# Sheet1.net
KiCad netlist of a schematic drawn in Altium Designer
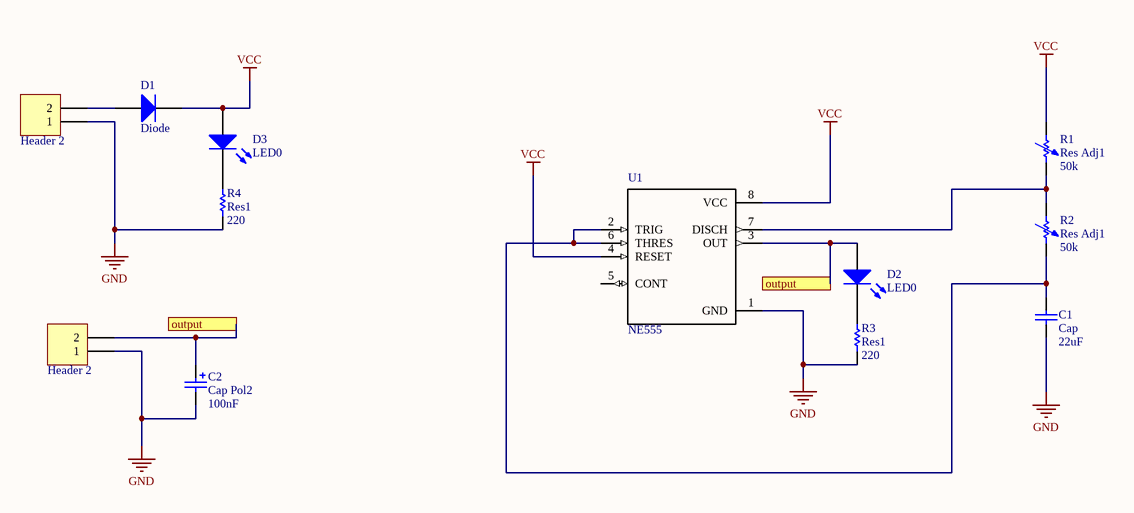
[diagram p0: Sheet1.SchDoc]

(export (version "E")
  (design (tool "Eeschema 10.0.6"))
  (components
    (comp (ref "C1")
      (value "Cap")
      (footprint "RAD-0.2")
      (description "Capacitor")
      (fields (field (name "ALTIUM_VALUE") "22uF") (field (name "PUBLISHER") "Altium Limited"))
      (libsource (lib "Miscellaneous Devices") (part "Cap"))
    )
    (comp (ref "C2")
      (value "Cap Pol2")
      (footprint "RAD-0.2")
      (description "Polarized Capacitor (Axial)")
      (fields (field (name "ALTIUM_VALUE") "100nF") (field (name "PUBLISHER") "Altium Limited"))
      (libsource (lib "Miscellaneous Devices") (part "Cap Pol2"))
    )
    (comp (ref "D1")
      (value "Diode")
      (footprint "DIODE-0.4")
      (description "Default Diode")
      (fields (field (name "PUBLISHER") "Altium Limited"))
      (libsource (lib "Miscellaneous Devices") (part "Diode"))
    )
    (comp (ref "D2")
      (value "LED0")
      (footprint "HDR1X2")
      (description "Typical INFRARED GaAs LED")
      (fields (field (name "PUBLISHER") "Altium Limited"))
      (libsource (lib "Miscellaneous Devices") (part "LED0"))
    )
    (comp (ref "D3")
      (value "LED0")
      (footprint "HDR1X2")
      (description "Typical INFRARED GaAs LED")
      (fields (field (name "PUBLISHER") "Altium Limited"))
      (libsource (lib "Miscellaneous Devices") (part "LED0"))
    )
    (comp (ref "P1")
      (value "Header 2")
      (footprint "CN_KRE_2")
      (description "Header, 2-Pin")
      (fields (field (name "PUBLISHER") "Altium Limited"))
      (libsource (lib "Miscellaneous Connectors") (part "Header 2"))
    )
    (comp (ref "P2")
      (value "Header 2")
      (footprint "CN_KRE_2")
      (description "Header, 2-Pin")
      (fields (field (name "PUBLISHER") "Altium Limited"))
      (libsource (lib "Miscellaneous Connectors") (part "Header 2"))
    )
    (comp (ref "R1")
      (value "Res Adj1")
      (footprint "CN_KRE_3")
      (description "Variable Resistor")
      (fields (field (name "ALTIUM_VALUE") "50k") (field (name "PUBLISHER") "Altium Limited"))
      (libsource (lib "Miscellaneous Devices") (part "Res Adj1"))
    )
    (comp (ref "R2")
      (value "Res Adj1")
      (footprint "CN_KRE_3")
      (description "Variable Resistor")
      (fields (field (name "ALTIUM_VALUE") "50k") (field (name "PUBLISHER") "Altium Limited"))
      (libsource (lib "Miscellaneous Devices") (part "Res Adj1"))
    )
    (comp (ref "R3")
      (value "Res1")
      (footprint "AXIAL-0.3")
      (description "Resistor")
      (fields (field (name "ALTIUM_VALUE") "220") (field (name "PUBLISHER") "Altium Limited"))
      (libsource (lib "Miscellaneous Devices") (part "Res1"))
    )
    (comp (ref "R4")
      (value "Res1")
      (footprint "AXIAL-0.3")
      (description "Resistor")
      (fields (field (name "ALTIUM_VALUE") "220") (field (name "PUBLISHER") "Altium Limited"))
      (libsource (lib "Miscellaneous Devices") (part "Res1"))
    )
    (comp (ref "U1")
      (value "NE555")
      (footprint "*DIP794W45P254L1060H508Q8")
      (fields (field (name "MF") "Texas Instruments") (field (name "DIGI-KEY_PART_NUMBER") "296-6501-1-ND"))
      (libsource (lib "NE555") (part "NE555"))
    )
  )
  (nets
    (net (code "1") (name "/output") (class "Default")
      (node (ref "C2") (pin "1") (pinfunction "1_1") (pintype "passive"))
      (node (ref "D2") (pin "1") (pinfunction "A_1") (pintype "passive"))
      (node (ref "P2") (pin "2") (pinfunction "2_2") (pintype "passive"))
      (node (ref "U1") (pin "3") (pinfunction "OUT_3") (pintype "output"))
    )
    (net (code "2") (name "GND") (class "Default")
      (node (ref "C1") (pin "1") (pinfunction "1_1") (pintype "passive"))
      (node (ref "C2") (pin "2") (pinfunction "2_2") (pintype "passive"))
      (node (ref "P1") (pin "1") (pinfunction "1_1") (pintype "passive"))
      (node (ref "P2") (pin "1") (pinfunction "1_1") (pintype "passive"))
      (node (ref "R3") (pin "1") (pinfunction "1_1") (pintype "passive"))
      (node (ref "R4") (pin "1") (pinfunction "1_1") (pintype "passive"))
      (node (ref "U1") (pin "1") (pinfunction "GND_1") (pintype "power_in"))
    )
    (net (code "3") (name "Net-(D1-A)") (class "Default")
      (node (ref "D1") (pin "1") (pinfunction "A_1") (pintype "passive"))
      (node (ref "P1") (pin "2") (pinfunction "2_2") (pintype "passive"))
    )
    (net (code "4") (name "Net-(D2-K)") (class "Default")
      (node (ref "D2") (pin "2") (pinfunction "K_2") (pintype "passive"))
      (node (ref "R3") (pin "2") (pinfunction "2_2") (pintype "passive"))
    )
    (net (code "5") (name "Net-(D3-K)") (class "Default")
      (node (ref "D3") (pin "2") (pinfunction "K_2") (pintype "passive"))
      (node (ref "R4") (pin "2") (pinfunction "2_2") (pintype "passive"))
    )
    (net (code "6") (name "Net-(U1-DISCH)") (class "Default")
      (node (ref "R1") (pin "2") (pinfunction "2_2") (pintype "passive"))
      (node (ref "R2") (pin "1") (pinfunction "1_1") (pintype "passive"))
      (node (ref "U1") (pin "7") (pinfunction "DISCH_7") (pintype "output"))
    )
    (net (code "7") (name "Net-(U1-THRES)") (class "Default")
      (node (ref "C1") (pin "2") (pinfunction "2_2") (pintype "passive"))
      (node (ref "R2") (pin "2") (pinfunction "2_2") (pintype "passive"))
      (node (ref "U1") (pin "2") (pinfunction "TRIG_2") (pintype "input"))
      (node (ref "U1") (pin "6") (pinfunction "THRES_6") (pintype "input"))
    )
    (net (code "8") (name "VCC") (class "Default")
      (node (ref "D1") (pin "2") (pinfunction "K_2") (pintype "passive"))
      (node (ref "D3") (pin "1") (pinfunction "A_1") (pintype "passive"))
      (node (ref "R1") (pin "1") (pinfunction "1_1") (pintype "passive"))
      (node (ref "U1") (pin "4") (pinfunction "RESET_4") (pintype "input"))
      (node (ref "U1") (pin "8") (pinfunction "VCC_8") (pintype "power_in"))
    )
    (net (code "9") (name "unconnected-(U1-CONT-Pad5)") (class "Default")
      (node (ref "U1") (pin "5") (pinfunction "CONT_5") (pintype "bidirectional"))
    )
  )
)
